# 04_-_COMMUNICATION.net
KiCad netlist of a schematic drawn in Altium Designer
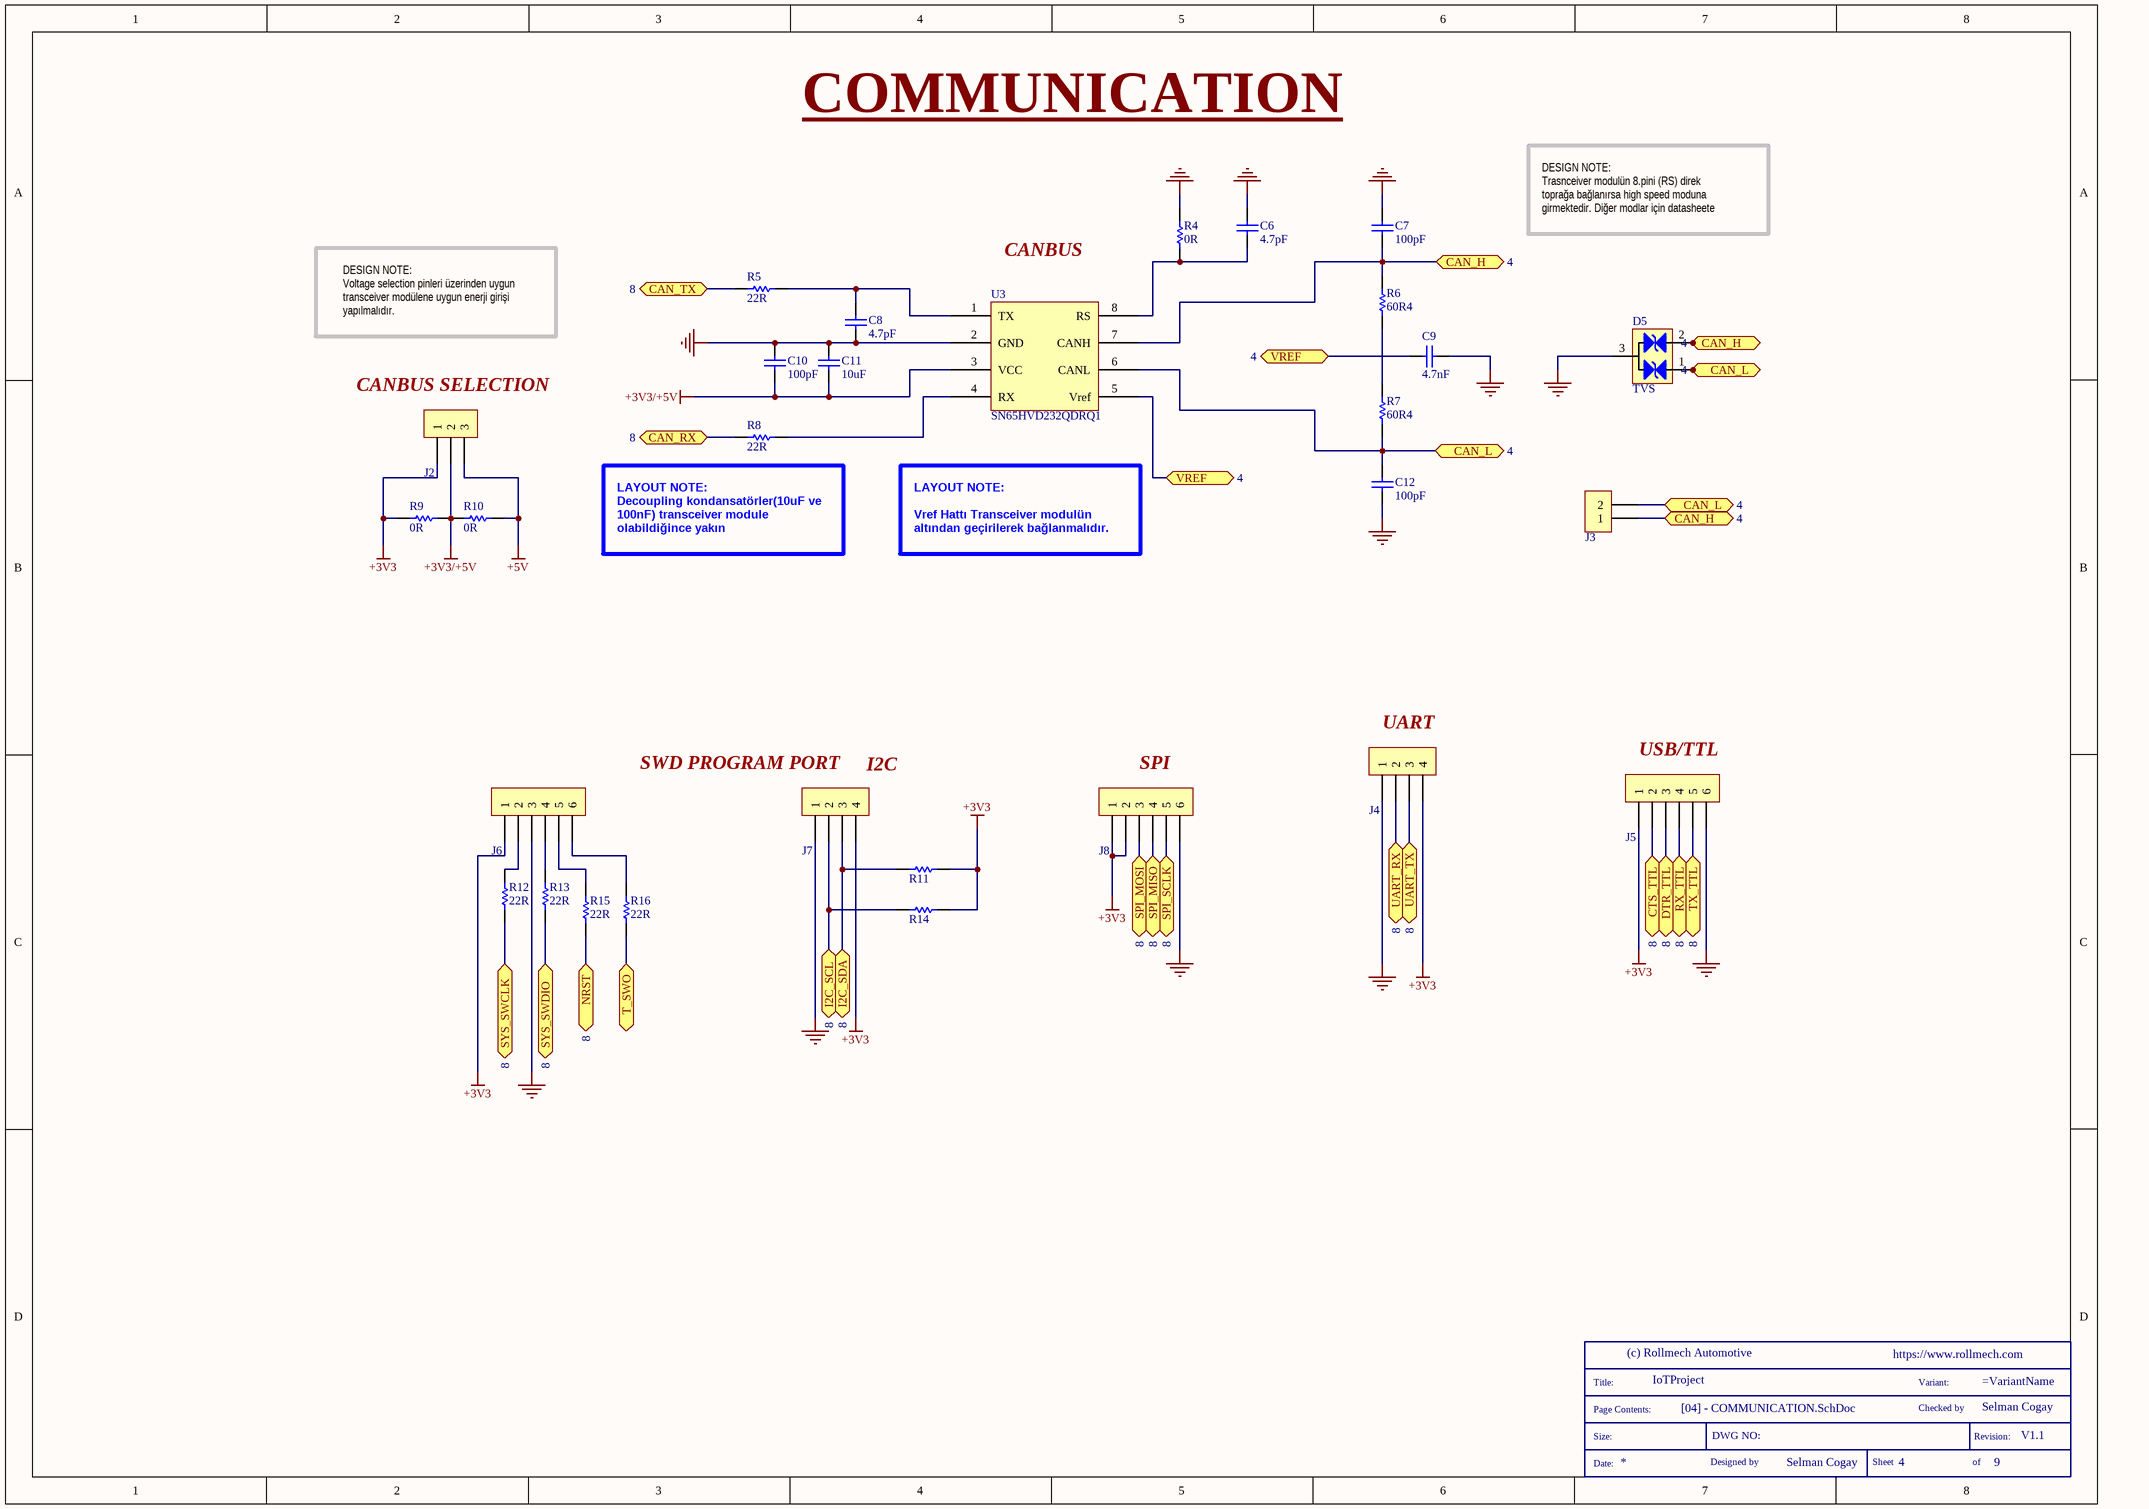
[diagram p0: [04] - COMMUNICATION.SchDoc]

(export (version "E")
  (design (tool "Eeschema 10.0.6"))
  (components
    (comp (ref "C6")
      (value "4.7pF")
      (footprint "C0603")
      (description "CAP CER 4.7PF 50V C0G 0603")
      (libsource (lib "SN65HVD2xx-CAN-Module-V1I1") (part "CGA3E2C0G1H4R7C080AA"))
    )
    (comp (ref "C7")
      (value "100pF")
      (footprint "C0805")
      (description "CAP CER 100PF 100V C0G 0805")
      (libsource (lib "SN65HVD2xx-CAN-Module-V1I1") (part "CGJ4C2C0G2A101J060AA"))
    )
    (comp (ref "C8")
      (value "4.7pF")
      (footprint "C0603")
      (description "CAP CER 4.7PF 50V C0G 0603")
      (libsource (lib "SN65HVD2xx-CAN-Module-V1I1") (part "CGA3E2C0G1H4R7C080AA"))
    )
    (comp (ref "C9")
      (value "4.7nF")
      (footprint "C0603")
      (description "CAP CER 4700PF 50V X7R 0603")
      (libsource (lib "SN65HVD2xx-CAN-Module-V1I1") (part "CGA3E2X7R1H472K080AA"))
    )
    (comp (ref "C10")
      (value "100pF")
      (footprint "C0805")
      (description "CAP CER 100PF 100V C0G 0805")
      (libsource (lib "SN65HVD2xx-CAN-Module-V1I1") (part "CGJ4C2C0G2A101J060AA"))
    )
    (comp (ref "C11")
      (value "10uF")
      (footprint "C0805")
      (description "CAP CER 10UF 10V X5R 0805")
      (libsource (lib "SN65HVD2xx-CAN-Module-V1I1") (part "CGA4J3X5R1A106K125AB"))
    )
    (comp (ref "C12")
      (value "100pF")
      (footprint "C0805")
      (description "CAP CER 100PF 100V C0G 0805")
      (libsource (lib "SN65HVD2xx-CAN-Module-V1I1") (part "CGJ4C2C0G2A101J060AA"))
    )
    (comp (ref "D5")
      (value "TVS")
      (footprint "SOT23-3")
      (description "TVS DIODE 24V 40V SOT23-3")
      (libsource (lib "SN65HVD2xx-CAN-Module-V1I1") (part "ESDCAN24-2BLY"))
    )
    (comp (ref "J2")
      (value "HDR_1X3_2.54")
      (footprint "HDR_MALE_1X3_2.54MM")
      (description "HDR MALE 1X3 2.54MM")
      (libsource (lib "Rollmech_Altium") (part "61300311121"))
    )
    (comp (ref "J3")
      (value "PPTC021LFBN-RC")
      (footprint "2POS_2.54mmPitch")
      (description "2POS 0.1 TIN PCB 2.54mm Pitch")
      (libsource (lib "IoTProject_V1.1") (part "PPTC021LFBN-RC"))
    )
    (comp (ref "J4")
      (value "HDR FEMALE 1X4 2.54MM")
      (footprint "HDR_FEMALE_1X4_2.54MM")
      (libsource (lib "Rollmech_Altium") (part "PPTC041LFBN-RC"))
    )
    (comp (ref "J5")
      (value "HDR FEMALE 1X6 2.54MM")
      (footprint "HDR_FEMALE_1X6_2.54MM")
      (libsource (lib "Rollmech_Altium") (part "PPTC061LFBN-RC"))
    )
    (comp (ref "J6")
      (value "HDR FEMALE 1X6 2.54MM")
      (footprint "HDR_FEMALE_1X6_2.54MM")
      (libsource (lib "Rollmech_Altium") (part "PPTC061LFBN-RC"))
    )
    (comp (ref "J7")
      (value "HDR FEMALE 1X4 2.54MM")
      (footprint "HDR_FEMALE_1X4_2.54MM")
      (libsource (lib "Rollmech_Altium") (part "PPTC041LFBN-RC"))
    )
    (comp (ref "J8")
      (value "HDR FEMALE 1X6 2.54MM")
      (footprint "HDR_FEMALE_1X6_2.54MM")
      (libsource (lib "Rollmech_Altium") (part "PPTC061LFBN-RC"))
    )
    (comp (ref "R4")
      (value "0R")
      (footprint "R0805")
      (description "RES SMD 0 OHM JUMPER 1/8W 0805")
      (libsource (lib "SN65HVD2xx-CAN-Module-V1I1") (part "CRCW08050000Z0EA"))
    )
    (comp (ref "R5")
      (value "22R")
      (footprint "R0805")
      (description "RES SMD 22 OHM 5% 1/8W 0805")
      (libsource (lib "SN65HVD2xx-CAN-Module-V1I1") (part "CRCW080522R0JNEA"))
    )
    (comp (ref "R6")
      (value "60R4")
      (footprint "R0805")
      (description "RES SMD 60.4 OHM 1% 1/8W 0805")
      (libsource (lib "SN65HVD2xx-CAN-Module-V1I1") (part "CRCW080560R4FKEA"))
    )
    (comp (ref "R7")
      (value "60R4")
      (footprint "R0805")
      (description "RES SMD 60.4 OHM 1% 1/8W 0805")
      (libsource (lib "SN65HVD2xx-CAN-Module-V1I1") (part "CRCW080560R4FKEA"))
    )
    (comp (ref "R8")
      (value "22R")
      (footprint "R0805")
      (description "RES SMD 22 OHM 5% 1/8W 0805")
      (libsource (lib "SN65HVD2xx-CAN-Module-V1I1") (part "CRCW080522R0JNEA"))
    )
    (comp (ref "R9")
      (value "0R")
      (footprint "R0805")
      (description "RES SMD 0 OHM JUMPER 1/8W 0805")
      (libsource (lib "SN65HVD2xx-CAN-Module-V1I1") (part "CRCW08050000Z0EA"))
    )
    (comp (ref "R10")
      (value "0R")
      (footprint "R0805")
      (description "RES SMD 0 OHM JUMPER 1/8W 0805")
      (libsource (lib "SN65HVD2xx-CAN-Module-V1I1") (part "CRCW08050000Z0EA"))
    )
    (comp (ref "R11")
      (value "5.6k 1/8W")
      (footprint "RES_0805")
      (description "RES SMD 5.6K OHM 1% 1/8W 0805")
      (libsource (lib "Rollmech_Altium") (part "ERJ-6ENF5601V"))
    )
    (comp (ref "R12")
      (value "22R")
      (footprint "R0805")
      (description "RES SMD 22 OHM 5% 1/8W 0805")
      (libsource (lib "SN65HVD2xx-CAN-Module-V1I1") (part "CRCW080522R0JNEA"))
    )
    (comp (ref "R13")
      (value "22R")
      (footprint "R0805")
      (description "RES SMD 22 OHM 5% 1/8W 0805")
      (libsource (lib "SN65HVD2xx-CAN-Module-V1I1") (part "CRCW080522R0JNEA"))
    )
    (comp (ref "R14")
      (value "5.6k 1/8W")
      (footprint "RES_0805")
      (description "RES SMD 5.6K OHM 1% 1/8W 0805")
      (libsource (lib "Rollmech_Altium") (part "ERJ-6ENF5601V"))
    )
    (comp (ref "R15")
      (value "22R")
      (footprint "R0805")
      (description "RES SMD 22 OHM 5% 1/8W 0805")
      (libsource (lib "SN65HVD2xx-CAN-Module-V1I1") (part "CRCW080522R0JNEA"))
    )
    (comp (ref "R16")
      (value "22R")
      (footprint "R0805")
      (description "RES SMD 22 OHM 5% 1/8W 0805")
      (libsource (lib "SN65HVD2xx-CAN-Module-V1I1") (part "CRCW080522R0JNEA"))
    )
    (comp (ref "U3")
      (value "SN65HVD232QDRQ1")
      (footprint "SOIC8")
      (description "IC TXRX CAN 1MBPS 3.3V 8SOIC")
      (libsource (lib "SN65HVD2xx-CAN-Module-V1I1") (part "SN65HVD232QDRQ1"))
    )
  )
  (nets
    (net (code "1") (name "+3V3") (class "Default")
      (node (ref "J2") (pin "1") (pinfunction "1_1") (pintype "passive"))
      (node (ref "J4") (pin "4") (pinfunction "4_4") (pintype "passive"))
      (node (ref "J5") (pin "1") (pinfunction "1_1") (pintype "passive"))
      (node (ref "J6") (pin "1") (pinfunction "1_1") (pintype "passive"))
      (node (ref "J7") (pin "4") (pinfunction "4_4") (pintype "passive"))
      (node (ref "J8") (pin "1") (pinfunction "1_1") (pintype "passive"))
      (node (ref "J8") (pin "2") (pinfunction "2_2") (pintype "passive"))
      (node (ref "R11") (pin "2") (pinfunction "2_2") (pintype "passive"))
      (node (ref "R14") (pin "2") (pinfunction "2_2") (pintype "passive"))
      (node (ref "R9") (pin "1") (pinfunction "1_1") (pintype "passive"))
    )
    (net (code "2") (name "+3V3{slash}+5V") (class "Default")
      (node (ref "C10") (pin "1") (pinfunction "1_1") (pintype "passive"))
      (node (ref "C11") (pin "1") (pinfunction "1_1") (pintype "passive"))
      (node (ref "J2") (pin "2") (pinfunction "2_2") (pintype "passive"))
      (node (ref "R10") (pin "2") (pinfunction "2_2") (pintype "passive"))
      (node (ref "R9") (pin "2") (pinfunction "2_2") (pintype "passive"))
      (node (ref "U3") (pin "3") (pinfunction "VCC_3") (pintype "passive"))
    )
    (net (code "3") (name "+5V") (class "Default")
      (node (ref "J2") (pin "3") (pinfunction "3_3") (pintype "passive"))
      (node (ref "R10") (pin "1") (pinfunction "1_1") (pintype "passive"))
    )
    (net (code "4") (name "/CAN_H") (class "Default")
      (node (ref "C7") (pin "1") (pinfunction "1_1") (pintype "passive"))
      (node (ref "J3") (pin "1") (pinfunction "1_1") (pintype "passive"))
      (node (ref "R6") (pin "2") (pinfunction "2_2") (pintype "passive"))
      (node (ref "U3") (pin "7") (pinfunction "CANH_7") (pintype "passive"))
    )
    (net (code "5") (name "/CAN_L") (class "Default")
      (node (ref "C12") (pin "2") (pinfunction "2_2") (pintype "passive"))
      (node (ref "J3") (pin "2") (pinfunction "2_2") (pintype "passive"))
      (node (ref "R7") (pin "1") (pinfunction "1_1") (pintype "passive"))
      (node (ref "U3") (pin "6") (pinfunction "CANL_6") (pintype "passive"))
    )
    (net (code "6") (name "/CAN_RX") (class "Default")
      (node (ref "R8") (pin "1") (pinfunction "1_1") (pintype "passive"))
    )
    (net (code "7") (name "/CAN_TX") (class "Default")
      (node (ref "R5") (pin "1") (pinfunction "1_1") (pintype "passive"))
    )
    (net (code "8") (name "/CTS_TTL") (class "Default")
      (node (ref "J5") (pin "2") (pinfunction "2_2") (pintype "passive"))
    )
    (net (code "9") (name "/DTR_TTL") (class "Default")
      (node (ref "J5") (pin "3") (pinfunction "3_3") (pintype "passive"))
    )
    (net (code "10") (name "/I2C_SCL") (class "Default")
      (node (ref "J7") (pin "2") (pinfunction "2_2") (pintype "passive"))
      (node (ref "R14") (pin "1") (pinfunction "1_1") (pintype "passive"))
    )
    (net (code "11") (name "/I2C_SDA") (class "Default")
      (node (ref "J7") (pin "3") (pinfunction "3_3") (pintype "passive"))
      (node (ref "R11") (pin "1") (pinfunction "1_1") (pintype "passive"))
    )
    (net (code "12") (name "/NRST") (class "Default")
      (node (ref "R15") (pin "1") (pinfunction "1_1") (pintype "passive"))
    )
    (net (code "13") (name "/RX_TTL") (class "Default")
      (node (ref "J5") (pin "4") (pinfunction "4_4") (pintype "passive"))
    )
    (net (code "14") (name "/SPI_MISO") (class "Default")
      (node (ref "J8") (pin "4") (pinfunction "4_4") (pintype "passive"))
    )
    (net (code "15") (name "/SPI_MOSI") (class "Default")
      (node (ref "J8") (pin "3") (pinfunction "3_3") (pintype "passive"))
    )
    (net (code "16") (name "/SPI_SCLK") (class "Default")
      (node (ref "J8") (pin "5") (pinfunction "5_5") (pintype "passive"))
    )
    (net (code "17") (name "/SYS_SWCLK") (class "Default")
      (node (ref "R12") (pin "1") (pinfunction "1_1") (pintype "passive"))
    )
    (net (code "18") (name "/SYS_SWDIO") (class "Default")
      (node (ref "R13") (pin "1") (pinfunction "1_1") (pintype "passive"))
    )
    (net (code "19") (name "/TX_TTL") (class "Default")
      (node (ref "J5") (pin "5") (pinfunction "5_5") (pintype "passive"))
    )
    (net (code "20") (name "/T_SWO") (class "Default")
      (node (ref "R16") (pin "1") (pinfunction "1_1") (pintype "passive"))
    )
    (net (code "21") (name "/UART_RX") (class "Default")
      (node (ref "J4") (pin "2") (pinfunction "2_2") (pintype "passive"))
    )
    (net (code "22") (name "/UART_TX") (class "Default")
      (node (ref "J4") (pin "3") (pinfunction "3_3") (pintype "passive"))
    )
    (net (code "23") (name "/VREF") (class "Default")
      (node (ref "C9") (pin "1") (pinfunction "1_1") (pintype "passive"))
      (node (ref "U3") (pin "5") (pinfunction "Vref_5") (pintype "passive"))
    )
    (net (code "24") (name "GND") (class "Default")
      (node (ref "C10") (pin "2") (pinfunction "2_2") (pintype "passive"))
      (node (ref "C11") (pin "2") (pinfunction "2_2") (pintype "passive"))
      (node (ref "C12") (pin "1") (pinfunction "1_1") (pintype "passive"))
      (node (ref "C6") (pin "2") (pinfunction "2_2") (pintype "passive"))
      (node (ref "C7") (pin "2") (pinfunction "2_2") (pintype "passive"))
      (node (ref "C8") (pin "1") (pinfunction "1_1") (pintype "passive"))
      (node (ref "C9") (pin "2") (pinfunction "2_2") (pintype "passive"))
      (node (ref "D5") (pin "3") (pinfunction "3_3") (pintype "passive"))
      (node (ref "J4") (pin "1") (pinfunction "1_1") (pintype "passive"))
      (node (ref "J5") (pin "6") (pinfunction "6_6") (pintype "passive"))
      (node (ref "J6") (pin "3") (pinfunction "3_3") (pintype "passive"))
      (node (ref "J7") (pin "1") (pinfunction "1_1") (pintype "passive"))
      (node (ref "J8") (pin "6") (pinfunction "6_6") (pintype "passive"))
      (node (ref "R4") (pin "2") (pinfunction "2_2") (pintype "passive"))
      (node (ref "U3") (pin "2") (pinfunction "GND_2") (pintype "passive"))
    )
    (net (code "25") (name "Net-(J6-Pad2)") (class "Default")
      (node (ref "J6") (pin "2") (pinfunction "2_2") (pintype "passive"))
      (node (ref "R12") (pin "2") (pinfunction "2_2") (pintype "passive"))
    )
    (net (code "26") (name "Net-(J6-Pad4)") (class "Default")
      (node (ref "J6") (pin "4") (pinfunction "4_4") (pintype "passive"))
      (node (ref "R13") (pin "2") (pinfunction "2_2") (pintype "passive"))
    )
    (net (code "27") (name "Net-(J6-Pad5)") (class "Default")
      (node (ref "J6") (pin "5") (pinfunction "5_5") (pintype "passive"))
      (node (ref "R15") (pin "2") (pinfunction "2_2") (pintype "passive"))
    )
    (net (code "28") (name "Net-(J6-Pad6)") (class "Default")
      (node (ref "J6") (pin "6") (pinfunction "6_6") (pintype "passive"))
      (node (ref "R16") (pin "2") (pinfunction "2_2") (pintype "passive"))
    )
    (net (code "29") (name "Net-(R6-Pad1)") (class "Default")
      (node (ref "R6") (pin "1") (pinfunction "1_1") (pintype "passive"))
      (node (ref "R7") (pin "2") (pinfunction "2_2") (pintype "passive"))
    )
    (net (code "30") (name "Net-(U3-RS)") (class "Default")
      (node (ref "C6") (pin "1") (pinfunction "1_1") (pintype "passive"))
      (node (ref "R4") (pin "1") (pinfunction "1_1") (pintype "passive"))
      (node (ref "U3") (pin "8") (pinfunction "RS_8") (pintype "passive"))
    )
    (net (code "31") (name "Net-(U3-RX)") (class "Default")
      (node (ref "R8") (pin "2") (pinfunction "2_2") (pintype "passive"))
      (node (ref "U3") (pin "4") (pinfunction "RX_4") (pintype "passive"))
    )
    (net (code "32") (name "Net-(U3-TX)") (class "Default")
      (node (ref "C8") (pin "2") (pinfunction "2_2") (pintype "passive"))
      (node (ref "R5") (pin "2") (pinfunction "2_2") (pintype "passive"))
      (node (ref "U3") (pin "1") (pinfunction "TX_1") (pintype "passive"))
    )
    (net (code "33") (name "unconnected-(D5-Pad1)") (class "Default")
      (node (ref "D5") (pin "1") (pinfunction "1_1") (pintype "passive"))
    )
    (net (code "34") (name "unconnected-(D5-Pad2)") (class "Default")
      (node (ref "D5") (pin "2") (pinfunction "2_2") (pintype "passive"))
    )
  )
)
